# 12-_BLE_and_FLASH.net
KiCad netlist of a schematic drawn in Altium Designer
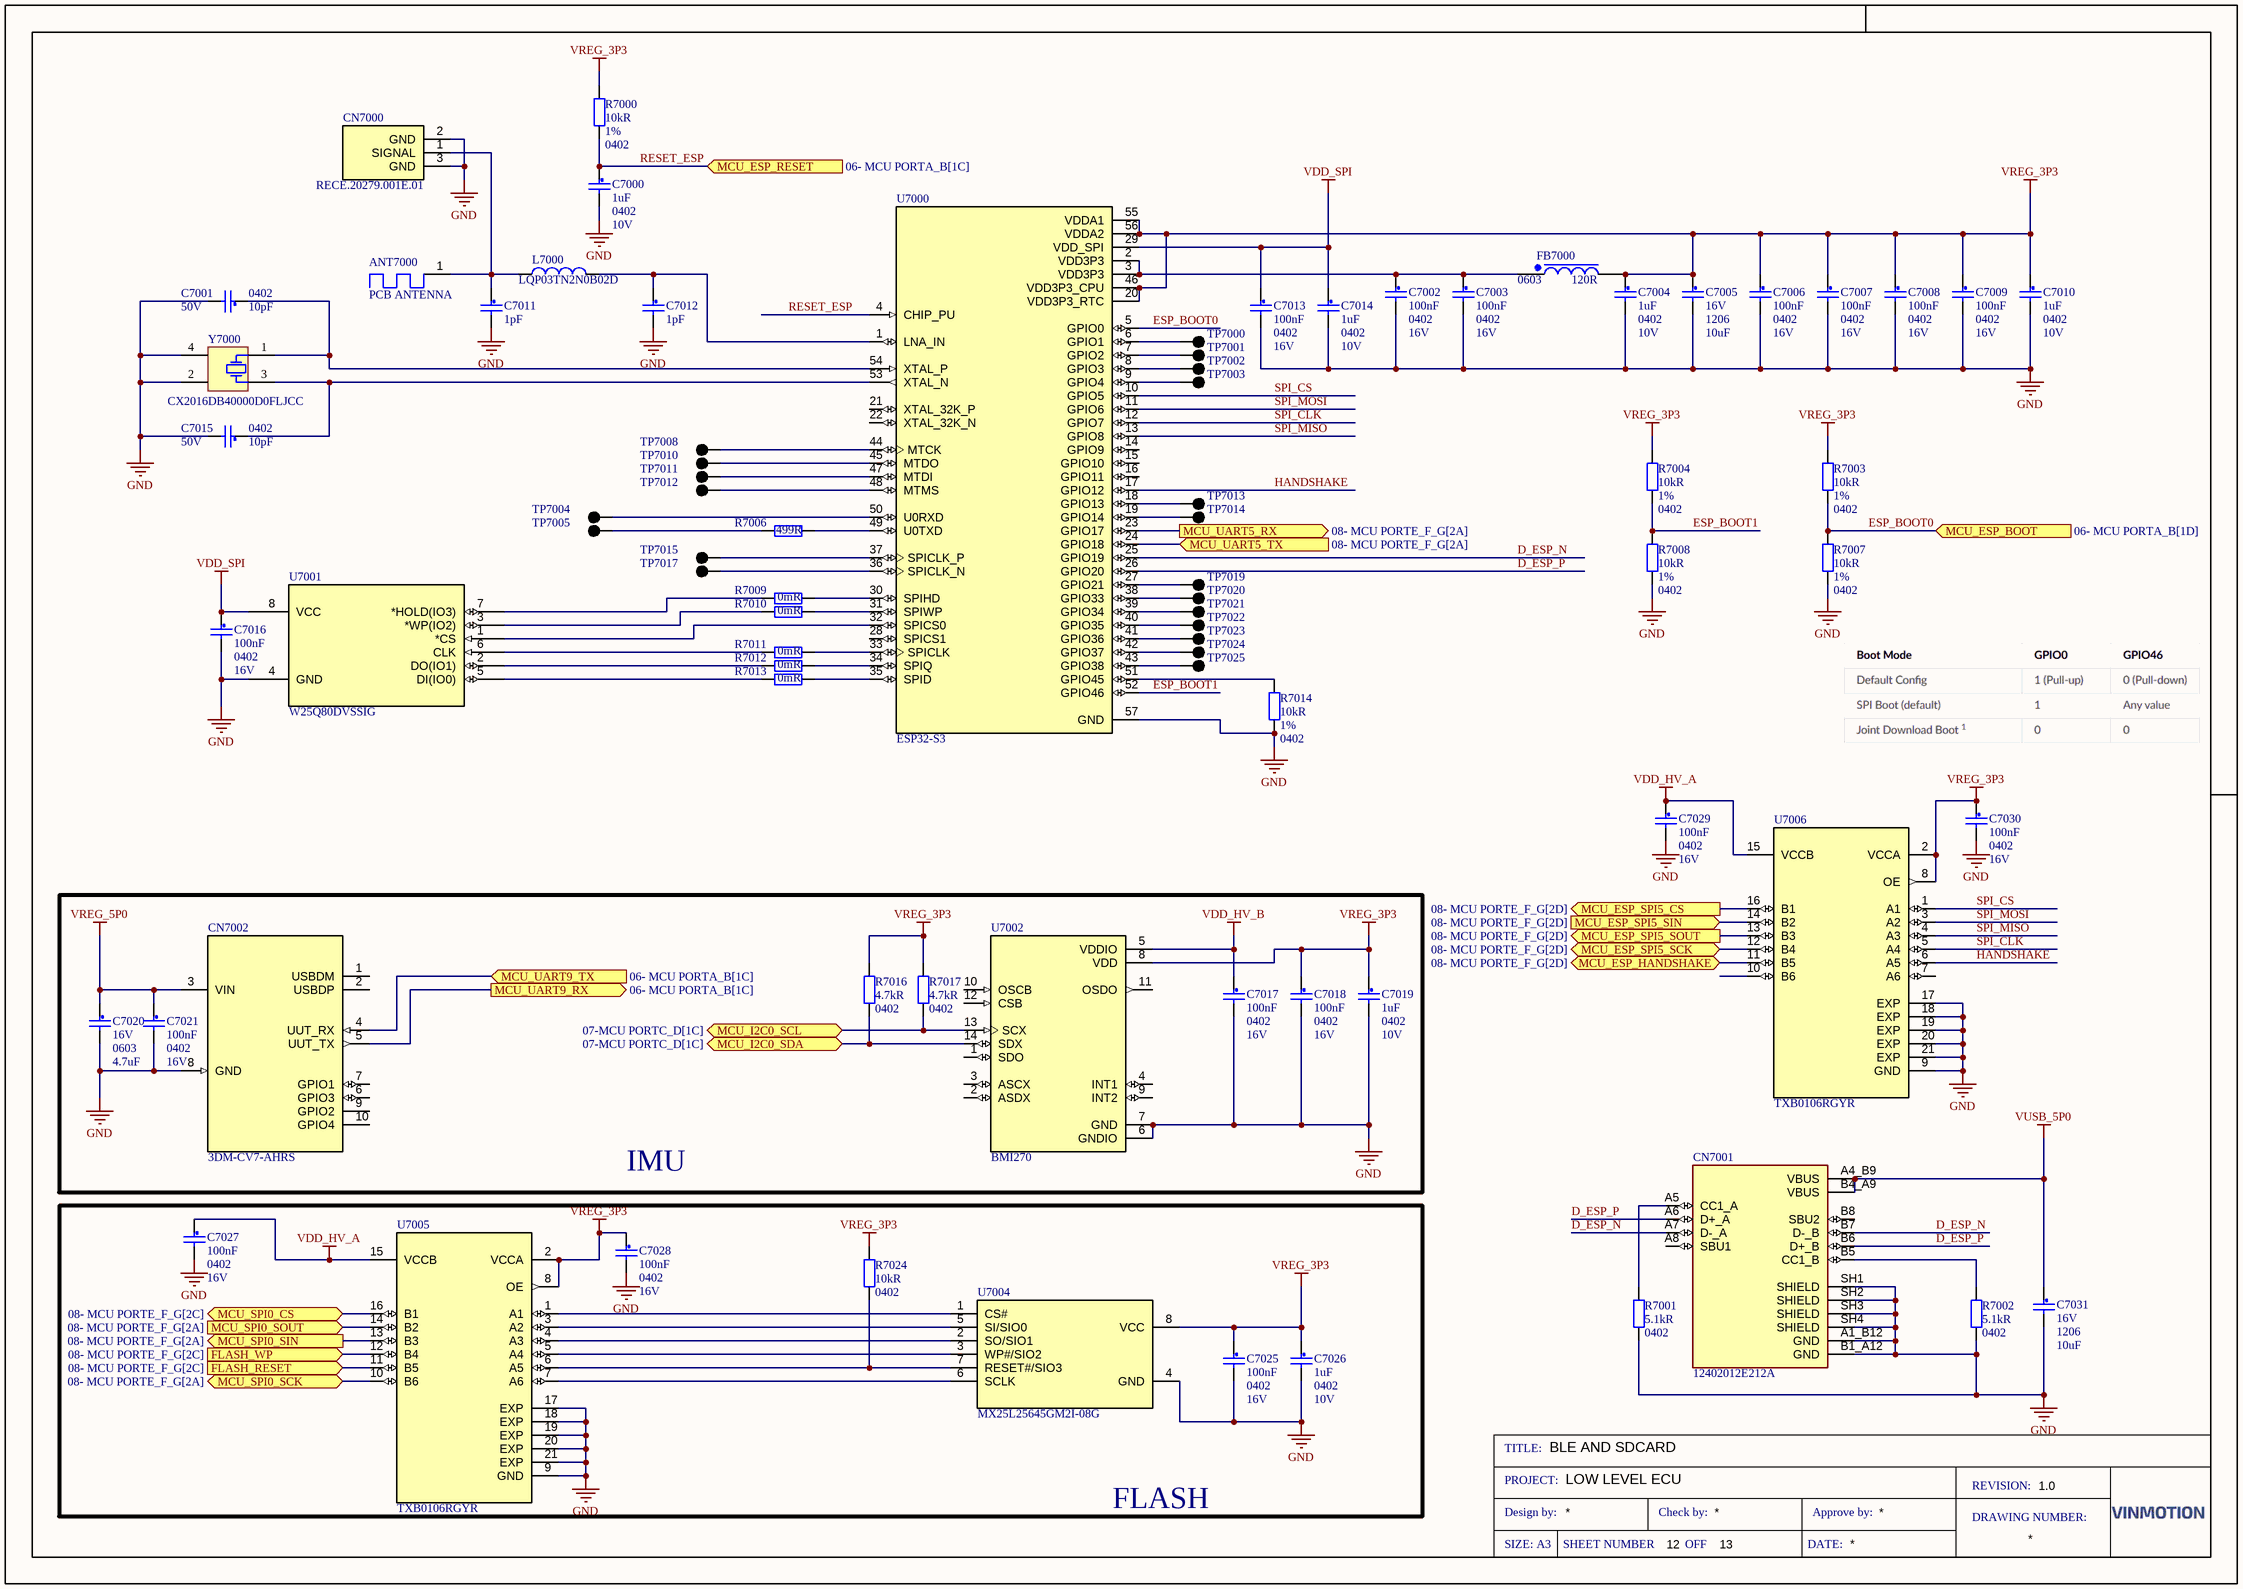
[diagram p0: 12- BLE and FLASH.SchDoc]

(export (version "E")
  (design (tool "Eeschema 10.0.6"))
  (components
    (comp (ref "ANT7000")
      (value "PCB ANTENNA")
      (footprint "ANTENNA 2.4G")
      (description "PCB ANTENNA 2.4G")
      (libsource (lib "VMO_Lib") (part "CMP-01139-1"))
    )
    (comp (ref "C7000")
      (value "1uF")
      (footprint "CAP0402")
      (description "CAP CER 1UF 10V X6S 0402")
      (fields
        (field (name "MANUFACTURER") "Samsung")
        (field (name "MANUFACTURER PART NUMBER") "CL05X105KP5NNNC")
        (field (name "CASE/PACKAGE") "0402")
        (field (name "RATED DC VOLTAGE (URDC)") "10V")
      )
      (libsource (lib "VMO_Lib") (part "CMP-01106-1"))
    )
    (comp (ref "C7001")
      (value "UMK105CG100DVHF")
      (footprint "CAP0402")
      (description "CAP CER 10pF 50V NP0 0402")
      (fields
        (field (name "VOLTAGE RATING") "50V")
        (field (name "CASE/PACKAGE") "0402")
        (field (name "CAPACITANCE") "10pF")
      )
      (libsource (lib "VMO_Lib") (part "CMP-00047-2"))
    )
    (comp (ref "C7002")
      (value "0402YC104KAT2A")
      (footprint "CAP0402")
      (description "CAP CER 0.1UF 16V X7R 0402")
      (fields
        (field (name "CAPACITANCE") "100nF")
        (field (name "CASE/PACKAGE") "0402")
        (field (name "VOLTAGE RATING (DC)") "16V")
      )
      (libsource (lib "VMO_Lib") (part "CMP-00988-1"))
    )
    (comp (ref "C7003")
      (value "0402YC104KAT2A")
      (footprint "CAP0402")
      (description "CAP CER 0.1UF 16V X7R 0402")
      (fields
        (field (name "CAPACITANCE") "100nF")
        (field (name "CASE/PACKAGE") "0402")
        (field (name "VOLTAGE RATING (DC)") "16V")
      )
      (libsource (lib "VMO_Lib") (part "CMP-00988-1"))
    )
    (comp (ref "C7004")
      (value "1uF")
      (footprint "CAP0402")
      (description "CAP CER 1UF 10V X6S 0402")
      (fields
        (field (name "MANUFACTURER") "Samsung")
        (field (name "MANUFACTURER PART NUMBER") "CL05X105KP5NNNC")
        (field (name "CASE/PACKAGE") "0402")
        (field (name "RATED DC VOLTAGE (URDC)") "10V")
      )
      (libsource (lib "VMO_Lib") (part "CMP-01106-1"))
    )
    (comp (ref "C7005")
      (value "CL31B106KOHVPNE")
      (footprint "CAP1206")
      (description "CAP CER 10uF 16V 10% X7R 1206 SMD")
      (fields
        (field (name "TOLERANCE") "10%")
        (field (name "VOLTAGE RATING") "16V")
        (field (name "CASE/PACKAGE") "1206")
        (field (name "CAPACITANCE") "10uF")
      )
      (libsource (lib "VMO_Lib") (part "CMP-00045-5"))
    )
    (comp (ref "C7006")
      (value "0402YC104KAT2A")
      (footprint "CAP0402")
      (description "CAP CER 0.1UF 16V X7R 0402")
      (fields
        (field (name "CAPACITANCE") "100nF")
        (field (name "CASE/PACKAGE") "0402")
        (field (name "VOLTAGE RATING (DC)") "16V")
      )
      (libsource (lib "VMO_Lib") (part "CMP-00988-1"))
    )
    (comp (ref "C7007")
      (value "0402YC104KAT2A")
      (footprint "CAP0402")
      (description "CAP CER 0.1UF 16V X7R 0402")
      (fields
        (field (name "CAPACITANCE") "100nF")
        (field (name "CASE/PACKAGE") "0402")
        (field (name "VOLTAGE RATING (DC)") "16V")
      )
      (libsource (lib "VMO_Lib") (part "CMP-00988-1"))
    )
    (comp (ref "C7008")
      (value "0402YC104KAT2A")
      (footprint "CAP0402")
      (description "CAP CER 0.1UF 16V X7R 0402")
      (fields
        (field (name "CAPACITANCE") "100nF")
        (field (name "CASE/PACKAGE") "0402")
        (field (name "VOLTAGE RATING (DC)") "16V")
      )
      (libsource (lib "VMO_Lib") (part "CMP-00988-1"))
    )
    (comp (ref "C7009")
      (value "0402YC104KAT2A")
      (footprint "CAP0402")
      (description "CAP CER 0.1UF 16V X7R 0402")
      (fields
        (field (name "CAPACITANCE") "100nF")
        (field (name "CASE/PACKAGE") "0402")
        (field (name "VOLTAGE RATING (DC)") "16V")
      )
      (libsource (lib "VMO_Lib") (part "CMP-00988-1"))
    )
    (comp (ref "C7010")
      (value "1uF")
      (footprint "CAP0402")
      (description "CAP CER 1UF 10V X6S 0402")
      (fields
        (field (name "MANUFACTURER") "Samsung")
        (field (name "MANUFACTURER PART NUMBER") "CL05X105KP5NNNC")
        (field (name "CASE/PACKAGE") "0402")
        (field (name "RATED DC VOLTAGE (URDC)") "10V")
      )
      (libsource (lib "VMO_Lib") (part "CMP-01106-1"))
    )
    (comp (ref "C7011")
      (value "1pF")
      (footprint "CAP0201")
      (description "CAP CER 1PF 50V C0G/NP0 0201")
      (fields
        (field (name "MANUFACTURER") "Murata")
        (field (name "MANUFACTURER PART NUMBER") "GRM0335C1H1R0BA01D")
      )
      (libsource (lib "VMO_Lib") (part "CMP-01137-1"))
    )
    (comp (ref "C7012")
      (value "1pF")
      (footprint "CAP0201")
      (description "CAP CER 1PF 50V C0G/NP0 0201")
      (fields
        (field (name "MANUFACTURER") "Murata")
        (field (name "MANUFACTURER PART NUMBER") "GRM0335C1H1R0BA01D")
      )
      (libsource (lib "VMO_Lib") (part "CMP-01137-1"))
    )
    (comp (ref "C7013")
      (value "0402YC104KAT2A")
      (footprint "CAP0402")
      (description "CAP CER 0.1UF 16V X7R 0402")
      (fields
        (field (name "CAPACITANCE") "100nF")
        (field (name "CASE/PACKAGE") "0402")
        (field (name "VOLTAGE RATING (DC)") "16V")
      )
      (libsource (lib "VMO_Lib") (part "CMP-00988-1"))
    )
    (comp (ref "C7014")
      (value "1uF")
      (footprint "CAP0402")
      (description "CAP CER 1UF 10V X6S 0402")
      (fields
        (field (name "MANUFACTURER") "Samsung")
        (field (name "MANUFACTURER PART NUMBER") "CL05X105KP5NNNC")
        (field (name "CASE/PACKAGE") "0402")
        (field (name "RATED DC VOLTAGE (URDC)") "10V")
      )
      (libsource (lib "VMO_Lib") (part "CMP-01106-1"))
    )
    (comp (ref "C7015")
      (value "UMK105CG100DVHF")
      (footprint "CAP0402")
      (description "CAP CER 10pF 50V NP0 0402")
      (fields
        (field (name "VOLTAGE RATING") "50V")
        (field (name "CASE/PACKAGE") "0402")
        (field (name "CAPACITANCE") "10pF")
      )
      (libsource (lib "VMO_Lib") (part "CMP-00047-2"))
    )
    (comp (ref "C7016")
      (value "0402YC104KAT2A")
      (footprint "CAP0402")
      (description "CAP CER 0.1UF 16V X7R 0402")
      (fields
        (field (name "CAPACITANCE") "100nF")
        (field (name "CASE/PACKAGE") "0402")
        (field (name "VOLTAGE RATING (DC)") "16V")
      )
      (libsource (lib "VMO_Lib") (part "CMP-00988-1"))
    )
    (comp (ref "C7017")
      (value "0402YC104KAT2A")
      (footprint "CAP0402")
      (description "CAP CER 0.1UF 16V X7R 0402")
      (fields
        (field (name "CAPACITANCE") "100nF")
        (field (name "CASE/PACKAGE") "0402")
        (field (name "VOLTAGE RATING (DC)") "16V")
      )
      (libsource (lib "VMO_Lib") (part "CMP-00988-1"))
    )
    (comp (ref "C7018")
      (value "0402YC104KAT2A")
      (footprint "CAP0402")
      (description "CAP CER 0.1UF 16V X7R 0402")
      (fields
        (field (name "CAPACITANCE") "100nF")
        (field (name "CASE/PACKAGE") "0402")
        (field (name "VOLTAGE RATING (DC)") "16V")
      )
      (libsource (lib "VMO_Lib") (part "CMP-00988-1"))
    )
    (comp (ref "C7019")
      (value "1uF")
      (footprint "CAP0402")
      (description "CAP CER 1UF 10V X6S 0402")
      (fields
        (field (name "MANUFACTURER") "Samsung")
        (field (name "MANUFACTURER PART NUMBER") "CL05X105KP5NNNC")
        (field (name "CASE/PACKAGE") "0402")
        (field (name "RATED DC VOLTAGE (URDC)") "10V")
      )
      (libsource (lib "VMO_Lib") (part "CMP-01106-1"))
    )
    (comp (ref "C7020")
      (value "GRT188C81C475KE13D")
      (footprint "CAP0603")
      (description "CAP CER 4.7uF 16V 10% X6S 0603 SMD")
      (fields
        (field (name "TOLERANCE") "10%")
        (field (name "VOLTAGE RATING") "16V")
        (field (name "CASE/PACKAGE") "0603")
        (field (name "CAPACITANCE") "4.7uF")
      )
      (libsource (lib "VMO_Lib") (part "CMP-00351-2"))
    )
    (comp (ref "C7021")
      (value "0402YC104KAT2A")
      (footprint "CAP0402")
      (description "CAP CER 0.1UF 16V X7R 0402")
      (fields
        (field (name "CAPACITANCE") "100nF")
        (field (name "CASE/PACKAGE") "0402")
        (field (name "VOLTAGE RATING (DC)") "16V")
      )
      (libsource (lib "VMO_Lib") (part "CMP-00988-1"))
    )
    (comp (ref "C7025")
      (value "0402YC104KAT2A")
      (footprint "CAP0402")
      (description "CAP CER 0.1UF 16V X7R 0402")
      (fields
        (field (name "CAPACITANCE") "100nF")
        (field (name "CASE/PACKAGE") "0402")
        (field (name "VOLTAGE RATING (DC)") "16V")
      )
      (libsource (lib "VMO_Lib") (part "CMP-00988-1"))
    )
    (comp (ref "C7026")
      (value "1uF")
      (footprint "CAP0402")
      (description "CAP CER 1UF 10V X6S 0402")
      (fields
        (field (name "MANUFACTURER") "Samsung")
        (field (name "MANUFACTURER PART NUMBER") "CL05X105KP5NNNC")
        (field (name "CASE/PACKAGE") "0402")
        (field (name "RATED DC VOLTAGE (URDC)") "10V")
      )
      (libsource (lib "VMO_Lib") (part "CMP-01106-1"))
    )
    (comp (ref "C7027")
      (value "0402YC104KAT2A")
      (footprint "CAP0402")
      (description "CAP CER 0.1UF 16V X7R 0402")
      (fields
        (field (name "CAPACITANCE") "100nF")
        (field (name "CASE/PACKAGE") "0402")
        (field (name "VOLTAGE RATING (DC)") "16V")
      )
      (libsource (lib "VMO_Lib") (part "CMP-00988-1"))
    )
    (comp (ref "C7028")
      (value "0402YC104KAT2A")
      (footprint "CAP0402")
      (description "CAP CER 0.1UF 16V X7R 0402")
      (fields
        (field (name "CAPACITANCE") "100nF")
        (field (name "CASE/PACKAGE") "0402")
        (field (name "VOLTAGE RATING (DC)") "16V")
      )
      (libsource (lib "VMO_Lib") (part "CMP-00988-1"))
    )
    (comp (ref "C7029")
      (value "0402YC104KAT2A")
      (footprint "CAP0402")
      (description "CAP CER 0.1UF 16V X7R 0402")
      (fields
        (field (name "CAPACITANCE") "100nF")
        (field (name "CASE/PACKAGE") "0402")
        (field (name "VOLTAGE RATING (DC)") "16V")
      )
      (libsource (lib "VMO_Lib") (part "CMP-00988-1"))
    )
    (comp (ref "C7030")
      (value "0402YC104KAT2A")
      (footprint "CAP0402")
      (description "CAP CER 0.1UF 16V X7R 0402")
      (fields
        (field (name "CAPACITANCE") "100nF")
        (field (name "CASE/PACKAGE") "0402")
        (field (name "VOLTAGE RATING (DC)") "16V")
      )
      (libsource (lib "VMO_Lib") (part "CMP-00988-1"))
    )
    (comp (ref "C7031")
      (value "CL31B106KOHVPNE")
      (footprint "CAP0603")
      (description "CAP CER 10uF 16V 10% X7R 1206 SMD")
      (fields
        (field (name "TOLERANCE") "10%")
        (field (name "VOLTAGE RATING") "16V")
        (field (name "CASE/PACKAGE") "1206")
        (field (name "CAPACITANCE") "10uF")
      )
      (libsource (lib "VMO_Lib") (part "CMP-00045-5"))
    )
    (comp (ref "CN7000")
      (value "RECE.20279.001E.01")
      (footprint "IPEX CONNECTOR")
      (description "CONN UMC RCPT STR 50 OHM SMD")
      (fields (field (name "MANUFACTURER") "Taoglas"))
      (libsource (lib "VMO_Lib") (part "CMP-01147-1"))
    )
    (comp (ref "CN7001")
      (value "12402012E212A")
      (footprint "USB_TYPE_C")
      (description "CONN RCP USB2.0 TYP C 24P SMD RA")
      (fields (field (name "MANUFACTURER") "Amphenol"))
      (libsource (lib "VMO_Lib") (part "CMP-01116-1"))
    )
    (comp (ref "CN7002")
      (value "3DM-CV7-AHRS")
      (footprint "3DM-CV7-AHRS")
      (description "IMUs - Inertial Measurement Units High Performance OEM IMU/AHRS")
      (fields (field (name "MANUFACTURER") "LORD"))
      (libsource (lib "VMO_Lib") (part "CMP-01131-1"))
    )
    (comp (ref "FB7000")
      (value "BLM18KG121TH1D")
      (footprint "FB0603")
      (description "FERRITE BEAD 120 OHM 0603 1LN")
      (fields (field (name "CASE/PACKAGE") "0603") (field (name "IMPEDANCE") "120R"))
      (libsource (lib "VMO_Lib") (part "CMP-ROOT-0013-6"))
    )
    (comp (ref "L7000")
      (value "LQP03TN2N0B02D")
      (footprint "IND0201")
      (description "FIXED IND 2NH 600MA 150 MOHM SMD")
      (fields (field (name "MANUFACTURER") "Murata") (field (name "TOLERANCE") "5%"))
      (libsource (lib "VMO_Lib") (part "CMP-01138-1"))
    )
    (comp (ref "R7000")
      (value "10kR")
      (footprint "RES0402")
      (description "RES 10K OHM 1% 1/16W 0402")
      (fields
        (field (name "MANUFACTURER") "Stackpole Electronics")
        (field (name "MANUFACTURER PART NUMBER") "RMCF0402FT10K0")
        (field (name "TOLERANCE") "1%")
        (field (name "CASE/PACKAGE") "0402")
      )
      (libsource (lib "VMO_Lib") (part "CMP-01105-1"))
    )
    (comp (ref "R7001")
      (value "MCR01MZPF5101")
      (footprint "RES0402")
      (description "RES SMD 5.1K OHM 1% 1/16W 0402")
      (fields
        (field (name "TOLERANCE") "1%")
        (field (name "RESISTANCE") "5.1kR")
        (field (name "CASE/PACKAGE") "0402")
      )
      (libsource (lib "VMO_Lib") (part "CMP-00289-1"))
    )
    (comp (ref "R7002")
      (value "MCR01MZPF5101")
      (footprint "RES0402")
      (description "RES SMD 5.1K OHM 1% 1/16W 0402")
      (fields
        (field (name "TOLERANCE") "1%")
        (field (name "RESISTANCE") "5.1kR")
        (field (name "CASE/PACKAGE") "0402")
      )
      (libsource (lib "VMO_Lib") (part "CMP-00289-1"))
    )
    (comp (ref "R7003")
      (value "10kR")
      (footprint "RES0402")
      (description "RES 10K OHM 1% 1/16W 0402")
      (fields
        (field (name "MANUFACTURER") "Stackpole Electronics")
        (field (name "MANUFACTURER PART NUMBER") "RMCF0402FT10K0")
        (field (name "TOLERANCE") "1%")
        (field (name "CASE/PACKAGE") "0402")
      )
      (libsource (lib "VMO_Lib") (part "CMP-01105-1"))
    )
    (comp (ref "R7004")
      (value "10kR")
      (footprint "RES0402")
      (description "RES 10K OHM 1% 1/16W 0402")
      (fields
        (field (name "MANUFACTURER") "Stackpole Electronics")
        (field (name "MANUFACTURER PART NUMBER") "RMCF0402FT10K0")
        (field (name "TOLERANCE") "1%")
        (field (name "CASE/PACKAGE") "0402")
      )
      (libsource (lib "VMO_Lib") (part "CMP-01105-1"))
    )
    (comp (ref "R7006")
      (value "499R")
      (footprint "RES0402")
      (description "RES SMD 499 OHM 1% 1/16W 0402")
      (fields
        (field (name "MANUFACTURER") "Vishay")
        (field (name "MANUFACTURER PART NUMBER") "CRCW0402499RFKED")
      )
      (libsource (lib "VMO_Lib") (part "CMP-01135-1"))
    )
    (comp (ref "R7007")
      (value "10kR")
      (footprint "RES0402")
      (description "RES 10K OHM 1% 1/16W 0402")
      (fields
        (field (name "MANUFACTURER") "Stackpole Electronics")
        (field (name "MANUFACTURER PART NUMBER") "RMCF0402FT10K0")
        (field (name "TOLERANCE") "1%")
        (field (name "CASE/PACKAGE") "0402")
      )
      (libsource (lib "VMO_Lib") (part "CMP-01105-1"))
    )
    (comp (ref "R7008")
      (value "10kR")
      (footprint "RES0402")
      (description "RES 10K OHM 1% 1/16W 0402")
      (fields
        (field (name "MANUFACTURER") "Stackpole Electronics")
        (field (name "MANUFACTURER PART NUMBER") "RMCF0402FT10K0")
        (field (name "TOLERANCE") "1%")
        (field (name "CASE/PACKAGE") "0402")
      )
      (libsource (lib "VMO_Lib") (part "CMP-01105-1"))
    )
    (comp (ref "R7009")
      (value "RMCF0402ZT0R00")
      (footprint "RES0402")
      (description "RES 0R 1/16W 1% 0402 SMD")
      (fields (field (name "RESISTANCE") "0mR"))
      (libsource (lib "VMO_Lib") (part "CMP-ROOT-0037-10"))
    )
    (comp (ref "R7010")
      (value "RMCF0402ZT0R00")
      (footprint "RES0402")
      (description "RES 0R 1/16W 1% 0402 SMD")
      (fields (field (name "RESISTANCE") "0mR"))
      (libsource (lib "VMO_Lib") (part "CMP-ROOT-0037-10"))
    )
    (comp (ref "R7011")
      (value "RMCF0402ZT0R00")
      (footprint "RES0402")
      (description "RES 0R 1/16W 1% 0402 SMD")
      (fields (field (name "RESISTANCE") "0mR"))
      (libsource (lib "VMO_Lib") (part "CMP-ROOT-0037-10"))
    )
    (comp (ref "R7012")
      (value "RMCF0402ZT0R00")
      (footprint "RES0402")
      (description "RES 0R 1/16W 1% 0402 SMD")
      (fields (field (name "RESISTANCE") "0mR"))
      (libsource (lib "VMO_Lib") (part "CMP-ROOT-0037-10"))
    )
    (comp (ref "R7013")
      (value "RMCF0402ZT0R00")
      (footprint "RES0402")
      (description "RES 0R 1/16W 1% 0402 SMD")
      (fields (field (name "RESISTANCE") "0mR"))
      (libsource (lib "VMO_Lib") (part "CMP-ROOT-0037-10"))
    )
    (comp (ref "R7014")
      (value "10kR")
      (footprint "RES0402")
      (description "RES 10K OHM 1% 1/16W 0402")
      (fields
        (field (name "MANUFACTURER") "Stackpole Electronics")
        (field (name "MANUFACTURER PART NUMBER") "RMCF0402FT10K0")
        (field (name "TOLERANCE") "1%")
        (field (name "CASE/PACKAGE") "0402")
      )
      (libsource (lib "VMO_Lib") (part "CMP-01105-1"))
    )
    (comp (ref "R7016")
      (value "RMCF0402FT4K70")
      (footprint "RES0402")
      (description "RES 4.7kR 1/16W 1% 0402 SMD")
      (fields
        (field (name "TOLERANCE") "1%")
        (field (name "RESISTANCE") "4.7kR")
        (field (name "CASE/PACKAGE") "0402")
      )
      (libsource (lib "VMO_Lib") (part "CMP-00354-2"))
    )
    (comp (ref "R7017")
      (value "RMCF0402FT4K70")
      (footprint "RES0402")
      (description "RES 4.7kR 1/16W 1% 0402 SMD")
      (fields
        (field (name "TOLERANCE") "1%")
        (field (name "RESISTANCE") "4.7kR")
        (field (name "CASE/PACKAGE") "0402")
      )
      (libsource (lib "VMO_Lib") (part "CMP-00354-2"))
    )
    (comp (ref "R7024")
      (value "ERJ2GEJ103X")
      (footprint "RES0402")
      (description "RES SMD 10K OHM 5% 1/10W 0402")
      (fields
        (field (name "TOLERANCE") "5%")
        (field (name "RESISTANCE") "10kR")
        (field (name "CASE/PACKAGE") "0402")
      )
      (libsource (lib "VMO_Lib") (part "CMP-00039-6"))
    )
    (comp (ref "TP7000")
      (value "TP")
      (footprint "TP-SMD-R1")
      (description "Test Point 1x1mm")
      (libsource (lib "VMO_Lib") (part "CMP-ROOT-0080-12"))
    )
    (comp (ref "TP7001")
      (value "TP")
      (footprint "TP-SMD-R1")
      (description "Test Point 1x1mm")
      (libsource (lib "VMO_Lib") (part "CMP-ROOT-0080-12"))
    )
    (comp (ref "TP7002")
      (value "TP")
      (footprint "TP-SMD-R1")
      (description "Test Point 1x1mm")
      (libsource (lib "VMO_Lib") (part "CMP-ROOT-0080-12"))
    )
    (comp (ref "TP7003")
      (value "TP")
      (footprint "TP-SMD-R1")
      (description "Test Point 1x1mm")
      (libsource (lib "VMO_Lib") (part "CMP-ROOT-0080-12"))
    )
    (comp (ref "TP7004")
      (value "TP")
      (footprint "TP-SMD-R1")
      (description "Test Point 1x1mm")
      (libsource (lib "VMO_Lib") (part "CMP-ROOT-0080-12"))
    )
    (comp (ref "TP7005")
      (value "TP")
      (footprint "TP-SMD-R1")
      (description "Test Point 1x1mm")
      (libsource (lib "VMO_Lib") (part "CMP-ROOT-0080-12"))
    )
    (comp (ref "TP7008")
      (value "TP")
      (footprint "TP-SMD-R1")
      (description "Test Point 1x1mm")
      (libsource (lib "VMO_Lib") (part "CMP-ROOT-0080-12"))
    )
    (comp (ref "TP7010")
      (value "TP")
      (footprint "TP-SMD-R1")
      (description "Test Point 1x1mm")
      (libsource (lib "VMO_Lib") (part "CMP-ROOT-0080-12"))
    )
    (comp (ref "TP7011")
      (value "TP")
      (footprint "TP-SMD-R1")
      (description "Test Point 1x1mm")
      (libsource (lib "VMO_Lib") (part "CMP-ROOT-0080-12"))
    )
    (comp (ref "TP7012")
      (value "TP")
      (footprint "TP-SMD-R1")
      (description "Test Point 1x1mm")
      (libsource (lib "VMO_Lib") (part "CMP-ROOT-0080-12"))
    )
    (comp (ref "TP7013")
      (value "TP")
      (footprint "TP-SMD-R1")
      (description "Test Point 1x1mm")
      (libsource (lib "VMO_Lib") (part "CMP-ROOT-0080-12"))
    )
    (comp (ref "TP7014")
      (value "TP")
      (footprint "TP-SMD-R1")
      (description "Test Point 1x1mm")
      (libsource (lib "VMO_Lib") (part "CMP-ROOT-0080-12"))
    )
    (comp (ref "TP7015")
      (value "TP")
      (footprint "TP-SMD-R1")
      (description "Test Point 1x1mm")
      (libsource (lib "VMO_Lib") (part "CMP-ROOT-0080-12"))
    )
    (comp (ref "TP7017")
      (value "TP")
      (footprint "TP-SMD-R1")
      (description "Test Point 1x1mm")
      (libsource (lib "VMO_Lib") (part "CMP-ROOT-0080-12"))
    )
    (comp (ref "TP7019")
      (value "TP")
      (footprint "TP-SMD-R1")
      (description "Test Point 1x1mm")
      (libsource (lib "VMO_Lib") (part "CMP-ROOT-0080-12"))
    )
    (comp (ref "TP7020")
      (value "TP")
      (footprint "TP-SMD-R1")
      (description "Test Point 1x1mm")
      (libsource (lib "VMO_Lib") (part "CMP-ROOT-0080-12"))
    )
    (comp (ref "TP7021")
      (value "TP")
      (footprint "TP-SMD-R1")
      (description "Test Point 1x1mm")
      (libsource (lib "VMO_Lib") (part "CMP-ROOT-0080-12"))
    )
    (comp (ref "TP7022")
      (value "TP")
      (footprint "TP-SMD-R1")
      (description "Test Point 1x1mm")
      (libsource (lib "VMO_Lib") (part "CMP-ROOT-0080-12"))
    )
    (comp (ref "TP7023")
      (value "TP")
      (footprint "TP-SMD-R1")
      (description "Test Point 1x1mm")
      (libsource (lib "VMO_Lib") (part "CMP-ROOT-0080-12"))
    )
    (comp (ref "TP7024")
      (value "TP")
      (footprint "TP-SMD-R1")
      (description "Test Point 1x1mm")
      (libsource (lib "VMO_Lib") (part "CMP-ROOT-0080-12"))
    )
    (comp (ref "TP7025")
      (value "TP")
      (footprint "TP-SMD-R1")
      (description "Test Point 1x1mm")
      (libsource (lib "VMO_Lib") (part "CMP-ROOT-0080-12"))
    )
    (comp (ref "U7000")
      (value "ESP32-S3")
      (footprint "56-VFQFN Exposed Pad")
      (description "IC RF TXRX+MCU BLE 56QFN")
      (fields
        (field (name "MANUFACTURER") "Espressif Systems")
        (field (name "MANUFACTURER PART NUMBER") "ESP32-S3R8")
      )
      (libsource (lib "VMO_Lib") (part "CMP-01132-1"))
    )
    (comp (ref "U7001")
      (value "W25Q80DVSSIG")
      (footprint "SOIC127P800X216-8N")
      (description "IC FLASH 8MBIT SPI/QUAD 8SOIC")
      (fields (field (name "MANUFACTURER") "Winbond"))
      (libsource (lib "VMO_Lib") (part "CMP-01134-1"))
    )
    (comp (ref "U7002")
      (value "BMI270")
      (footprint "BIN270")
      (description "IMU ACCEL/GYRO I2C/SPI 14LGA")
      (fields (field (name "MANUFACTURER") "Bosch Sensortec"))
      (libsource (lib "VMO_Lib") (part "CMP-01130-1"))
    )
    (comp (ref "U7004")
      (value "MX25L25645GM2I-08G")
      (footprint "SOIC127P800X175-8N")
      (description "IC FLASH 256MBIT SPI 120MHZ 8SOP")
      (fields (field (name "MANUFACTURER") "Macronix"))
      (libsource (lib "VMO_Lib") (part "CMP-01188-1"))
    )
    (comp (ref "U7005")
      (value "TXB0106RGYR")
      (footprint "16-VFQFN Exposed Pad")
      (description "IC VOLTAGE LEVEL BIDIR 16-VQFN")
      (fields (field (name "MANUFACTURER") "Texas Instruments"))
      (libsource (lib "VMO_Lib") (part "CMP-01197-1"))
    )
    (comp (ref "U7006")
      (value "TXB0106RGYR")
      (footprint "16-VFQFN Exposed Pad")
      (description "IC VOLTAGE LEVEL BIDIR 16-VQFN")
      (fields (field (name "MANUFACTURER") "Texas Instruments"))
      (libsource (lib "VMO_Lib") (part "CMP-01197-1"))
    )
    (comp (ref "Y7000")
      (value "CX2016DB40000D0FLJCC")
      (footprint "CRYSTAL2016")
      (description "CRYSTAL 40.0000MHZ 8PF SMD")
      (fields (field (name "MANUFACTURER") "Kyocera AVX"))
      (libsource (lib "VMO_Lib") (part "CMP-01136-1"))
    )
  )
  (nets
    (net (code "1") (name "/D_ESP_N") (class "Default")
      (node (ref "CN7001") (pin "A7") (pinfunction "D-_A_A7") (pintype "bidirectional"))
      (node (ref "CN7001") (pin "B7") (pinfunction "D-_B_B7") (pintype "bidirectional"))
      (node (ref "U7000") (pin "25") (pinfunction "GPIO19_25") (pintype "bidirectional"))
    )
    (net (code "2") (name "/D_ESP_P") (class "Default")
      (node (ref "CN7001") (pin "A6") (pinfunction "D+_A_A6") (pintype "bidirectional"))
      (node (ref "CN7001") (pin "B6") (pinfunction "D+_B_B6") (pintype "bidirectional"))
      (node (ref "U7000") (pin "26") (pinfunction "GPIO20_26") (pintype "bidirectional"))
    )
    (net (code "3") (name "/ESP_BOOT0") (class "Default")
      (node (ref "R7003") (pin "1") (pinfunction "1_1") (pintype "passive"))
      (node (ref "R7007") (pin "2") (pinfunction "2_2") (pintype "passive"))
      (node (ref "U7000") (pin "5") (pinfunction "GPIO0_5") (pintype "bidirectional"))
    )
    (net (code "4") (name "/ESP_BOOT1") (class "Default")
      (node (ref "R7004") (pin "1") (pinfunction "1_1") (pintype "passive"))
      (node (ref "R7008") (pin "2") (pinfunction "2_2") (pintype "passive"))
      (node (ref "U7000") (pin "52") (pinfunction "GPIO46_52") (pintype "bidirectional"))
    )
    (net (code "5") (name "/FLASH_RESET") (class "Default")
      (node (ref "U7005") (pin "11") (pinfunction "B5_11") (pintype "bidirectional"))
    )
    (net (code "6") (name "/FLASH_WP") (class "Default")
      (node (ref "U7005") (pin "12") (pinfunction "B4_12") (pintype "bidirectional"))
    )
    (net (code "7") (name "/HANDSHAKE") (class "Default")
      (node (ref "U7000") (pin "17") (pinfunction "GPIO12_17") (pintype "bidirectional"))
      (node (ref "U7006") (pin "6") (pinfunction "A5_6") (pintype "bidirectional"))
    )
    (net (code "8") (name "/MCU_ESP_HANDSHAKE") (class "Default")
      (node (ref "U7006") (pin "11") (pinfunction "B5_11") (pintype "bidirectional"))
    )
    (net (code "9") (name "/MCU_ESP_SPI5_CS") (class "Default")
      (node (ref "U7006") (pin "16") (pinfunction "B1_16") (pintype "bidirectional"))
    )
    (net (code "10") (name "/MCU_ESP_SPI5_SCK") (class "Default")
      (node (ref "U7006") (pin "12") (pinfunction "B4_12") (pintype "bidirectional"))
    )
    (net (code "11") (name "/MCU_ESP_SPI5_SIN") (class "Default")
      (node (ref "U7006") (pin "14") (pinfunction "B2_14") (pintype "bidirectional"))
    )
    (net (code "12") (name "/MCU_ESP_SPI5_SOUT") (class "Default")
      (node (ref "U7006") (pin "13") (pinfunction "B3_13") (pintype "bidirectional"))
    )
    (net (code "13") (name "/MCU_I2C0_SCL") (class "Default")
      (node (ref "R7017") (pin "1") (pinfunction "1_1") (pintype "passive"))
      (node (ref "U7002") (pin "13") (pinfunction "SCX_13") (pintype "input"))
    )
    (net (code "14") (name "/MCU_I2C0_SDA") (class "Default")
      (node (ref "R7016") (pin "1") (pinfunction "1_1") (pintype "passive"))
      (node (ref "U7002") (pin "14") (pinfunction "SDX_14") (pintype "bidirectional"))
    )
    (net (code "15") (name "/MCU_SPI0_CS") (class "Default")
      (node (ref "U7005") (pin "16") (pinfunction "B1_16") (pintype "bidirectional"))
    )
    (net (code "16") (name "/MCU_SPI0_SCK") (class "Default")
      (node (ref "U7005") (pin "10") (pinfunction "B6_10") (pintype "bidirectional"))
    )
    (net (code "17") (name "/MCU_SPI0_SIN") (class "Default")
      (node (ref "U7005") (pin "13") (pinfunction "B3_13") (pintype "bidirectional"))
    )
    (net (code "18") (name "/MCU_SPI0_SOUT") (class "Default")
      (node (ref "U7005") (pin "14") (pinfunction "B2_14") (pintype "bidirectional"))
    )
    (net (code "19") (name "/MCU_UART5_RX") (class "Default")
      (node (ref "U7000") (pin "23") (pinfunction "GPIO17_23") (pintype "bidirectional"))
    )
    (net (code "20") (name "/MCU_UART5_TX") (class "Default")
      (node (ref "U7000") (pin "24") (pinfunction "GPIO18_24") (pintype "bidirectional"))
    )
    (net (code "21") (name "/MCU_UART9_RX") (class "Default")
      (node (ref "CN7002") (pin "5") (pinfunction "UUT_TX_5") (pintype "output"))
    )
    (net (code "22") (name "/MCU_UART9_TX") (class "Default")
      (node (ref "CN7002") (pin "4") (pinfunction "UUT_RX_4") (pintype "input"))
    )
    (net (code "23") (name "/RESET_ESP") (class "Default")
      (node (ref "C7000") (pin "1") (pinfunction "1_1") (pintype "passive"))
      (node (ref "R7000") (pin "1") (pinfunction "1_1") (pintype "passive"))
      (node (ref "U7000") (pin "4") (pinfunction "CHIP_PU_4") (pintype "input"))
    )
    (net (code "24") (name "/SPI_CLK") (class "Default")
      (node (ref "U7000") (pin "12") (pinfunction "GPIO7_12") (pintype "bidirectional"))
      (node (ref "U7006") (pin "5") (pinfunction "A4_5") (pintype "bidirectional"))
    )
    (net (code "25") (name "/SPI_CS") (class "Default")
      (node (ref "U7000") (pin "10") (pinfunction "GPIO5_10") (pintype "bidirectional"))
      (node (ref "U7006") (pin "1") (pinfunction "A1_1") (pintype "bidirectional"))
    )
    (net (code "26") (name "/SPI_MISO") (class "Default")
      (node (ref "U7000") (pin "13") (pinfunction "GPIO8_13") (pintype "bidirectional"))
      (node (ref "U7006") (pin "4") (pinfunction "A3_4") (pintype "bidirectional"))
    )
    (net (code "27") (name "/SPI_MOSI") (class "Default")
      (node (ref "U7000") (pin "11") (pinfunction "GPIO6_11") (pintype "bidirectional"))
      (node (ref "U7006") (pin "3") (pinfunction "A2_3") (pintype "bidirectional"))
    )
    (net (code "28") (name "GND") (class "Default")
      (node (ref "C7000") (pin "2") (pinfunction "2_2") (pintype "passive"))
      (node (ref "C7001") (pin "2") (pinfunction "2_2") (pintype "passive"))
      (node (ref "C7002") (pin "2") (pinfunction "2_2") (pintype "passive"))
      (node (ref "C7003") (pin "2") (pinfunction "2_2") (pintype "passive"))
      (node (ref "C7004") (pin "2") (pinfunction "2_2") (pintype "passive"))
      (node (ref "C7005") (pin "2") (pinfunction "2_2") (pintype "passive"))
      (node (ref "C7006") (pin "2") (pinfunction "2_2") (pintype "passive"))
      (node (ref "C7007") (pin "2") (pinfunction "2_2") (pintype "passive"))
      (node (ref "C7008") (pin "2") (pinfunction "2_2") (pintype "passive"))
      (node (ref "C7009") (pin "2") (pinfunction "2_2") (pintype "passive"))
      (node (ref "C7010") (pin "2") (pinfunction "2_2") (pintype "passive"))
      (node (ref "C7011") (pin "2") (pinfunction "2_2") (pintype "passive"))
      (node (ref "C7012") (pin "2") (pinfunction "2_2") (pintype "passive"))
      (node (ref "C7013") (pin "2") (pinfunction "2_2") (pintype "passive"))
      (node (ref "C7014") (pin "2") (pinfunction "2_2") (pintype "passive"))
      (node (ref "C7015") (pin "2") (pinfunction "2_2") (pintype "passive"))
      (node (ref "C7016") (pin "2") (pinfunction "2_2") (pintype "passive"))
      (node (ref "C7017") (pin "2") (pinfunction "2_2") (pintype "passive"))
      (node (ref "C7018") (pin "2") (pinfunction "2_2") (pintype "passive"))
      (node (ref "C7019") (pin "2") (pinfunction "2_2") (pintype "passive"))
      (node (ref "C7020") (pin "2") (pinfunction "2_2") (pintype "passive"))
      (node (ref "C7021") (pin "2") (pinfunction "2_2") (pintype "passive"))
      (node (ref "C7025") (pin "2") (pinfunction "2_2") (pintype "passive"))
      (node (ref "C7026") (pin "2") (pinfunction "2_2") (pintype "passive"))
      (node (ref "C7027") (pin "2") (pinfunction "2_2") (pintype "passive"))
      (node (ref "C7028") (pin "2") (pinfunction "2_2") (pintype "passive"))
      (node (ref "C7029") (pin "2") (pinfunction "2_2") (pintype "passive"))
      (node (ref "C7030") (pin "2") (pinfunction "2_2") (pintype "passive"))
      (node (ref "C7031") (pin "2") (pinfunction "2_2") (pintype "passive"))
      (node (ref "CN7000") (pin "2") (pinfunction "GND_2") (pintype "passive"))
      (node (ref "CN7000") (pin "3") (pinfunction "GND_3") (pintype "passive"))
      (node (ref "CN7001") (pin "A1_B12") (pinfunction "GND_A1_B12") (pintype "power_in"))
      (node (ref "CN7001") (pin "B1_A12") (pinfunction "GND_B1_A12") (pintype "power_in"))
      (node (ref "CN7001") (pin "SH1") (pinfunction "SHIELD_SH1") (pintype "passive"))
      (node (ref "CN7001") (pin "SH2") (pinfunction "SHIELD_SH2") (pintype "passive"))
      (node (ref "CN7001") (pin "SH3") (pinfunction "SHIELD_SH3") (pintype "passive"))
      (node (ref "CN7001") (pin "SH4") (pinfunction "SHIELD_SH4") (pintype "passive"))
      (node (ref "CN7002") (pin "8") (pinfunction "GND_8") (pintype "input"))
      (node (ref "R7001") (pin "1") (pinfunction "1_1") (pintype "passive"))
      (node (ref "R7002") (pin "1") (pinfunction "1_1") (pintype "passive"))
      (node (ref "R7007") (pin "1") (pinfunction "1_1") (pintype "passive"))
      (node (ref "R7008") (pin "1") (pinfunction "1_1") (pintype "passive"))
      (node (ref "R7014") (pin "1") (pinfunction "1_1") (pintype "passive"))
      (node (ref "U7000") (pin "57") (pinfunction "GND_57") (pintype "power_in"))
      (node (ref "U7001") (pin "4") (pinfunction "GND_4") (pintype "power_in"))
      (node (ref "U7002") (pin "6") (pinfunction "GNDIO_6") (pintype "power_in"))
      (node (ref "U7002") (pin "7") (pinfunction "GND_7") (pintype "power_in"))
      (node (ref "U7004") (pin "4") (pinfunction "GND_4") (pintype "passive"))
      (node (ref "U7005") (pin "17") (pinfunction "EXP_17") (pintype "passive"))
      (node (ref "U7005") (pin "18") (pinfunction "EXP_18") (pintype "passive"))
      (node (ref "U7005") (pin "19") (pinfunction "EXP_19") (pintype "passive"))
      (node (ref "U7005") (pin "20") (pinfunction "EXP_20") (pintype "passive"))
      (node (ref "U7005") (pin "21") (pinfunction "EXP_21") (pintype "passive"))
      (node (ref "U7005") (pin "9") (pinfunction "GND_9") (pintype "power_in"))
      (node (ref "U7006") (pin "17") (pinfunction "EXP_17") (pintype "passive"))
      (node (ref "U7006") (pin "18") (pinfunction "EXP_18") (pintype "passive"))
      (node (ref "U7006") (pin "19") (pinfunction "EXP_19") (pintype "passive"))
      (node (ref "U7006") (pin "20") (pinfunction "EXP_20") (pintype "passive"))
      (node (ref "U7006") (pin "21") (pinfunction "EXP_21") (pintype "passive"))
      (node (ref "U7006") (pin "9") (pinfunction "GND_9") (pintype "power_in"))
      (node (ref "Y7000") (pin "2") (pinfunction "GND_2") (pintype "passive"))
      (node (ref "Y7000") (pin "4") (pinfunction "GND_4") (pintype "passive"))
    )
    (net (code "29") (name "Net-(ANT7000-ANT)") (class "Default")
      (node (ref "ANT7000") (pin "1") (pinfunction "ANT_1") (pintype "passive"))
      (node (ref "C7011") (pin "1") (pinfunction "1_1") (pintype "passive"))
      (node (ref "CN7000") (pin "1") (pinfunction "SIGNAL_1") (pintype "passive"))
      (node (ref "L7000") (pin "1") (pinfunction "1_1") (pintype "passive"))
    )
    (net (code "30") (name "Net-(C7002-Pad1)") (class "Default")
      (node (ref "C7002") (pin "1") (pinfunction "1_1") (pintype "passive"))
      (node (ref "C7003") (pin "1") (pinfunction "1_1") (pintype "passive"))
      (node (ref "FB7000") (pin "1") (pinfunction "1_1") (pintype "passive"))
      (node (ref "U7000") (pin "2") (pinfunction "VDD3P3_2") (pintype "power_in"))
      (node (ref "U7000") (pin "3") (pinfunction "VDD3P3_3") (pintype "power_in"))
    )
    (net (code "31") (name "Net-(CN7001-CC1_A)") (class "Default")
      (node (ref "CN7001") (pin "A5") (pinfunction "CC1_A_A5") (pintype "bidirectional"))
      (node (ref "R7001") (pin "2") (pinfunction "2_2") (pintype "passive"))
    )
    (net (code "32") (name "Net-(CN7001-CC1_B)") (class "Default")
      (node (ref "CN7001") (pin "B5") (pinfunction "CC1_B_B5") (pintype "bidirectional"))
      (node (ref "R7002") (pin "2") (pinfunction "2_2") (pintype "passive"))
    )
    (net (code "33") (name "Net-(R7006-Pad2)") (class "Default")
      (node (ref "R7006") (pin "2") (pinfunction "2_2") (pintype "passive"))
      (node (ref "TP7005") (pin "1") (pinfunction "1_1") (pintype "passive"))
    )
    (net (code "34") (name "Net-(U7000-GPIO1)") (class "Default")
      (node (ref "TP7000") (pin "1") (pinfunction "1_1") (pintype "passive"))
      (node (ref "U7000") (pin "6") (pinfunction "GPIO1_6") (pintype "bidirectional"))
    )
    (net (code "35") (name "Net-(U7000-GPIO2)") (class "Default")
      (node (ref "TP7001") (pin "1") (pinfunction "1_1") (pintype "passive"))
      (node (ref "U7000") (pin "7") (pinfunction "GPIO2_7") (pintype "bidirectional"))
    )
    (net (code "36") (name "Net-(U7000-GPIO3)") (class "Default")
      (node (ref "TP7002") (pin "1") (pinfunction "1_1") (pintype "passive"))
      (node (ref "U7000") (pin "8") (pinfunction "GPIO3_8") (pintype "bidirectional"))
    )
    (net (code "37") (name "Net-(U7000-GPIO4)") (class "Default")
      (node (ref "TP7003") (pin "1") (pinfunction "1_1") (pintype "passive"))
      (node (ref "U7000") (pin "9") (pinfunction "GPIO4_9") (pintype "bidirectional"))
    )
    (net (code "38") (name "Net-(U7000-GPIO13)") (class "Default")
      (node (ref "TP7013") (pin "1") (pinfunction "1_1") (pintype "passive"))
      (node (ref "U7000") (pin "18") (pinfunction "GPIO13_18") (pintype "bidirectional"))
    )
    (net (code "39") (name "Net-(U7000-GPIO14)") (class "Default")
      (node (ref "TP7014") (pin "1") (pinfunction "1_1") (pintype "passive"))
      (node (ref "U7000") (pin "19") (pinfunction "GPIO14_19") (pintype "bidirectional"))
    )
    (net (code "40") (name "Net-(U7000-GPIO21)") (class "Default")
      (node (ref "TP7019") (pin "1") (pinfunction "1_1") (pintype "passive"))
      (node (ref "U7000") (pin "27") (pinfunction "GPIO21_27") (pintype "bidirectional"))
    )
    (net (code "41") (name "Net-(U7000-GPIO33)") (class "Default")
      (node (ref "TP7020") (pin "1") (pinfunction "1_1") (pintype "passive"))
      (node (ref "U7000") (pin "38") (pinfunction "GPIO33_38") (pintype "bidirectional"))
    )
    (net (code "42") (name "Net-(U7000-GPIO34)") (class "Default")
      (node (ref "TP7021") (pin "1") (pinfunction "1_1") (pintype "passive"))
      (node (ref "U7000") (pin "39") (pinfunction "GPIO34_39") (pintype "bidirectional"))
    )
    (net (code "43") (name "Net-(U7000-GPIO35)") (class "Default")
      (node (ref "TP7022") (pin "1") (pinfunction "1_1") (pintype "passive"))
      (node (ref "U7000") (pin "40") (pinfunction "GPIO35_40") (pintype "bidirectional"))
    )
    (net (code "44") (name "Net-(U7000-GPIO36)") (class "Default")
      (node (ref "TP7023") (pin "1") (pinfunction "1_1") (pintype "passive"))
      (node (ref "U7000") (pin "41") (pinfunction "GPIO36_41") (pintype "bidirectional"))
    )
    (net (code "45") (name "Net-(U7000-GPIO37)") (class "Default")
      (node (ref "TP7024") (pin "1") (pinfunction "1_1") (pintype "passive"))
      (node (ref "U7000") (pin "42") (pinfunction "GPIO37_42") (pintype "bidirectional"))
    )
    (net (code "46") (name "Net-(U7000-GPIO38)") (class "Default")
      (node (ref "TP7025") (pin "1") (pinfunction "1_1") (pintype "passive"))
      (node (ref "U7000") (pin "43") (pinfunction "GPIO38_43") (pintype "bidirectional"))
    )
    (net (code "47") (name "Net-(U7000-GPIO45)") (class "Default")
      (node (ref "R7014") (pin "2") (pinfunction "2_2") (pintype "passive"))
      (node (ref "U7000") (pin "51") (pinfunction "GPIO45_51") (pintype "bidirectional"))
    )
    (net (code "48") (name "Net-(U7000-LNA_IN)") (class "Default")
      (node (ref "C7012") (pin "1") (pinfunction "1_1") (pintype "passive"))
      (node (ref "L7000") (pin "2") (pinfunction "2_2") (pintype "passive"))
      (node (ref "U7000") (pin "1") (pinfunction "LNA_IN_1") (pintype "bidirectional"))
    )
    (net (code "49") (name "Net-(U7000-MTCK)") (class "Default")
      (node (ref "TP7008") (pin "1") (pinfunction "1_1") (pintype "passive"))
      (node (ref "U7000") (pin "44") (pinfunction "MTCK_44") (pintype "bidirectional"))
    )
    (net (code "50") (name "Net-(U7000-MTDI)") (class "Default")
      (node (ref "TP7011") (pin "1") (pinfunction "1_1") (pintype "passive"))
      (node (ref "U7000") (pin "47") (pinfunction "MTDI_47") (pintype "bidirectional"))
    )
    (net (code "51") (name "Net-(U7000-MTDO)") (class "Default")
      (node (ref "TP7010") (pin "1") (pinfunction "1_1") (pintype "passive"))
      (node (ref "U7000") (pin "45") (pinfunction "MTDO_45") (pintype "bidirectional"))
    )
    (net (code "52") (name "Net-(U7000-MTMS)") (class "Default")
      (node (ref "TP7012") (pin "1") (pinfunction "1_1") (pintype "passive"))
      (node (ref "U7000") (pin "48") (pinfunction "MTMS_48") (pintype "bidirectional"))
    )
    (net (code "53") (name "Net-(U7000-SPICLK)") (class "Default")
      (node (ref "R7011") (pin "2") (pinfunction "2_2") (pintype "passive"))
      (node (ref "U7000") (pin "33") (pinfunction "SPICLK_33") (pintype "bidirectional"))
    )
    (net (code "54") (name "Net-(U7000-SPICLK_N)") (class "Default")
      (node (ref "TP7017") (pin "1") (pinfunction "1_1") (pintype "passive"))
      (node (ref "U7000") (pin "36") (pinfunction "SPICLK_N_36") (pintype "bidirectional"))
    )
    (net (code "55") (name "Net-(U7000-SPICLK_P)") (class "Default")
      (node (ref "TP7015") (pin "1") (pinfunction "1_1") (pintype "passive"))
      (node (ref "U7000") (pin "37") (pinfunction "SPICLK_P_37") (pintype "bidirectional"))
    )
    (net (code "56") (name "Net-(U7000-SPICS0)") (class "Default")
      (node (ref "U7000") (pin "32") (pinfunction "SPICS0_32") (pintype "bidirectional"))
      (node (ref "U7001") (pin "1") (pinfunction "*CS_1") (pintype "input"))
    )
    (net (code "57") (name "Net-(U7000-SPID)") (class "Default")
      (node (ref "R7013") (pin "2") (pinfunction "2_2") (pintype "passive"))
      (node (ref "U7000") (pin "35") (pinfunction "SPID_35") (pintype "bidirectional"))
    )
    (net (code "58") (name "Net-(U7000-SPIHD)") (class "Default")
      (node (ref "R7009") (pin "2") (pinfunction "2_2") (pintype "passive"))
      (node (ref "U7000") (pin "30") (pinfunction "SPIHD_30") (pintype "bidirectional"))
    )
    (net (code "59") (name "Net-(U7000-SPIQ)") (class "Default")
      (node (ref "R7012") (pin "2") (pinfunction "2_2") (pintype "passive"))
      (node (ref "U7000") (pin "34") (pinfunction "SPIQ_34") (pintype "bidirectional"))
    )
    (net (code "60") (name "Net-(U7000-SPIWP)") (class "Default")
      (node (ref "R7010") (pin "2") (pinfunction "2_2") (pintype "passive"))
      (node (ref "U7000") (pin "31") (pinfunction "SPIWP_31") (pintype "bidirectional"))
    )
    (net (code "61") (name "Net-(U7000-U0RXD)") (class "Default")
      (node (ref "TP7004") (pin "1") (pinfunction "1_1") (pintype "passive"))
      (node (ref "U7000") (pin "50") (pinfunction "U0RXD_50") (pintype "bidirectional"))
    )
    (net (code "62") (name "Net-(U7000-U0TXD)") (class "Default")
      (node (ref "R7006") (pin "1") (pinfunction "1_1") (pintype "passive"))
      (node (ref "U7000") (pin "49") (pinfunction "U0TXD_49") (pintype "bidirectional"))
    )
    (net (code "63") (name "Net-(U7000-XTAL_N)") (class "Default")
      (node (ref "C7015") (pin "1") (pinfunction "1_1") (pintype "passive"))
      (node (ref "U7000") (pin "53") (pinfunction "XTAL_N_53") (pintype "output"))
      (node (ref "Y7000") (pin "3") (pinfunction "OSC2_3") (pintype "passive"))
    )
    (net (code "64") (name "Net-(U7000-XTAL_P)") (class "Default")
      (node (ref "C7001") (pin "1") (pinfunction "1_1") (pintype "passive"))
      (node (ref "U7000") (pin "54") (pinfunction "XTAL_P_54") (pintype "input"))
      (node (ref "Y7000") (pin "1") (pinfunction "OSC1_1") (pintype "passive"))
    )
    (net (code "65") (name "Net-(U7001-*HOLD(IO3))") (class "Default")
      (node (ref "R7009") (pin "1") (pinfunction "1_1") (pintype "passive"))
      (node (ref "U7001") (pin "7") (pinfunction "*HOLD(IO3)_7") (pintype "bidirectional"))
    )
    (net (code "66") (name "Net-(U7001-*WP(IO2))") (class "Default")
      (node (ref "R7010") (pin "1") (pinfunction "1_1") (pintype "passive"))
      (node (ref "U7001") (pin "3") (pinfunction "*WP(IO2)_3") (pintype "bidirectional"))
    )
    (net (code "67") (name "Net-(U7001-CLK)") (class "Default")
      (node (ref "R7011") (pin "1") (pinfunction "1_1") (pintype "passive"))
      (node (ref "U7001") (pin "6") (pinfunction "CLK_6") (pintype "input"))
    )
    (net (code "68") (name "Net-(U7001-DI(IO0))") (class "Default")
      (node (ref "R7013") (pin "1") (pinfunction "1_1") (pintype "passive"))
      (node (ref "U7001") (pin "5") (pinfunction "DI(IO0)_5") (pintype "bidirectional"))
    )
    (net (code "69") (name "Net-(U7001-DO(IO1))") (class "Default")
      (node (ref "R7012") (pin "1") (pinfunction "1_1") (pintype "passive"))
      (node (ref "U7001") (pin "2") (pinfunction "DO(IO1)_2") (pintype "bidirectional"))
    )
    (net (code "70") (name "Net-(U7004-CS#)") (class "Default")
      (node (ref "U7004") (pin "1") (pinfunction "CS#_1") (pintype "passive"))
      (node (ref "U7005") (pin "1") (pinfunction "A1_1") (pintype "bidirectional"))
    )
    (net (code "71") (name "Net-(U7004-RESET#{slash}SIO3)") (class "Default")
      (node (ref "R7024") (pin "1") (pinfunction "1_1") (pintype "passive"))
      (node (ref "U7004") (pin "7") (pinfunction "RESET#/SIO3_7") (pintype "passive"))
      (node (ref "U7005") (pin "6") (pinfunction "A5_6") (pintype "bidirectional"))
    )
    (net (code "72") (name "Net-(U7004-SCLK)") (class "Default")
      (node (ref "U7004") (pin "6") (pinfunction "SCLK_6") (pintype "passive"))
      (node (ref "U7005") (pin "7") (pinfunction "A6_7") (pintype "bidirectional"))
    )
    (net (code "73") (name "Net-(U7004-SI{slash}SIO0)") (class "Default")
      (node (ref "U7004") (pin "5") (pinfunction "SI/SIO0_5") (pintype "passive"))
      (node (ref "U7005") (pin "3") (pinfunction "A2_3") (pintype "bidirectional"))
    )
    (net (code "74") (name "Net-(U7004-SO{slash}SIO1)") (class "Default")
      (node (ref "U7004") (pin "2") (pinfunction "SO/SIO1_2") (pintype "passive"))
      (node (ref "U7005") (pin "4") (pinfunction "A3_4") (pintype "bidirectional"))
    )
    (net (code "75") (name "Net-(U7004-WP#{slash}SIO2)") (class "Default")
      (node (ref "U7004") (pin "3") (pinfunction "WP#/SIO2_3") (pintype "passive"))
      (node (ref "U7005") (pin "5") (pinfunction "A4_5") (pintype "bidirectional"))
    )
    (net (code "76") (name "VDD_HV_A") (class "Default")
      (node (ref "C7027") (pin "1") (pinfunction "1_1") (pintype "passive"))
      (node (ref "C7029") (pin "1") (pinfunction "1_1") (pintype "passive"))
      (node (ref "U7005") (pin "15") (pinfunction "VCCB_15") (pintype "power_in"))
      (node (ref "U7006") (pin "15") (pinfunction "VCCB_15") (pintype "power_in"))
    )
    (net (code "77") (name "VDD_HV_B") (class "Default")
      (node (ref "C7017") (pin "1") (pinfunction "1_1") (pintype "passive"))
      (node (ref "U7002") (pin "5") (pinfunction "VDDIO_5") (pintype "power_in"))
    )
    (net (code "78") (name "VDD_SPI") (class "Default")
      (node (ref "C7013") (pin "1") (pinfunction "1_1") (pintype "passive"))
      (node (ref "C7014") (pin "1") (pinfunction "1_1") (pintype "passive"))
      (node (ref "C7016") (pin "1") (pinfunction "1_1") (pintype "passive"))
      (node (ref "U7000") (pin "29") (pinfunction "VDD_SPI_29") (pintype "power_in"))
      (node (ref "U7001") (pin "8") (pinfunction "VCC_8") (pintype "power_in"))
    )
    (net (code "79") (name "VREG_3P3") (class "Default")
      (node (ref "C7004") (pin "1") (pinfunction "1_1") (pintype "passive"))
      (node (ref "C7005") (pin "1") (pinfunction "1_1") (pintype "passive"))
      (node (ref "C7006") (pin "1") (pinfunction "1_1") (pintype "passive"))
      (node (ref "C7007") (pin "1") (pinfunction "1_1") (pintype "passive"))
      (node (ref "C7008") (pin "1") (pinfunction "1_1") (pintype "passive"))
      (node (ref "C7009") (pin "1") (pinfunction "1_1") (pintype "passive"))
      (node (ref "C7010") (pin "1") (pinfunction "1_1") (pintype "passive"))
      (node (ref "C7018") (pin "1") (pinfunction "1_1") (pintype "passive"))
      (node (ref "C7019") (pin "1") (pinfunction "1_1") (pintype "passive"))
      (node (ref "C7025") (pin "1") (pinfunction "1_1") (pintype "passive"))
      (node (ref "C7026") (pin "1") (pinfunction "1_1") (pintype "passive"))
      (node (ref "C7028") (pin "1") (pinfunction "1_1") (pintype "passive"))
      (node (ref "C7030") (pin "1") (pinfunction "1_1") (pintype "passive"))
      (node (ref "FB7000") (pin "2") (pinfunction "2_2") (pintype "passive"))
      (node (ref "R7000") (pin "2") (pinfunction "2_2") (pintype "passive"))
      (node (ref "R7003") (pin "2") (pinfunction "2_2") (pintype "passive"))
      (node (ref "R7004") (pin "2") (pinfunction "2_2") (pintype "passive"))
      (node (ref "R7016") (pin "2") (pinfunction "2_2") (pintype "passive"))
      (node (ref "R7017") (pin "2") (pinfunction "2_2") (pintype "passive"))
      (node (ref "R7024") (pin "2") (pinfunction "2_2") (pintype "passive"))
      (node (ref "U7000") (pin "20") (pinfunction "VDD3P3_RTC_20") (pintype "power_in"))
      (node (ref "U7000") (pin "46") (pinfunction "VDD3P3_CPU_46") (pintype "power_in"))
      (node (ref "U7000") (pin "55") (pinfunction "VDDA1_55") (pintype "power_in"))
      (node (ref "U7000") (pin "56") (pinfunction "VDDA2_56") (pintype "power_in"))
      (node (ref "U7002") (pin "8") (pinfunction "VDD_8") (pintype "power_in"))
      (node (ref "U7004") (pin "8") (pinfunction "VCC_8") (pintype "passive"))
      (node (ref "U7005") (pin "2") (pinfunction "VCCA_2") (pintype "power_in"))
      (node (ref "U7005") (pin "8") (pinfunction "OE_8") (pintype "output"))
      (node (ref "U7006") (pin "2") (pinfunction "VCCA_2") (pintype "power_in"))
      (node (ref "U7006") (pin "8") (pinfunction "OE_8") (pintype "output"))
    )
    (net (code "80") (name "VREG_5P0") (class "Default")
      (node (ref "C7020") (pin "1") (pinfunction "1_1") (pintype "passive"))
      (node (ref "C7021") (pin "1") (pinfunction "1_1") (pintype "passive"))
      (node (ref "CN7002") (pin "3") (pinfunction "VIN_3") (pintype "power_in"))
    )
    (net (code "81") (name "VUSB_5P0") (class "Default")
      (node (ref "C7031") (pin "1") (pinfunction "1_1") (pintype "passive"))
      (node (ref "CN7001") (pin "A4_B9") (pinfunction "VBUS_A4_B9") (pintype "power_in"))
      (node (ref "CN7001") (pin "B4_A9") (pinfunction "VBUS_B4_A9") (pintype "power_in"))
    )
    (net (code "82") (name "unconnected-(CN7001-SBU1-PadA8)") (class "Default")
      (node (ref "CN7001") (pin "A8") (pinfunction "SBU1_A8") (pintype "bidirectional"))
    )
    (net (code "83") (name "unconnected-(CN7001-SBU2-PadB8)") (class "Default")
      (node (ref "CN7001") (pin "B8") (pinfunction "SBU2_B8") (pintype "bidirectional"))
    )
    (net (code "84") (name "unconnected-(CN7002-GPIO1-Pad7)") (class "Default")
      (node (ref "CN7002") (pin "7") (pinfunction "GPIO1_7") (pintype "bidirectional"))
    )
    (net (code "85") (name "unconnected-(CN7002-GPIO2-Pad9)") (class "Default")
      (node (ref "CN7002") (pin "9") (pinfunction "GPIO2_9") (pintype "power_in"))
    )
    (net (code "86") (name "unconnected-(CN7002-GPIO3-Pad6)") (class "Default")
      (node (ref "CN7002") (pin "6") (pinfunction "GPIO3_6") (pintype "bidirectional"))
    )
    (net (code "87") (name "unconnected-(CN7002-GPIO4-Pad10)") (class "Default")
      (node (ref "CN7002") (pin "10") (pinfunction "GPIO4_10") (pintype "power_in"))
    )
    (net (code "88") (name "unconnected-(CN7002-USBDM-Pad1)") (class "Default")
      (node (ref "CN7002") (pin "1") (pinfunction "USBDM_1") (pintype "passive"))
    )
    (net (code "89") (name "unconnected-(CN7002-USBDP-Pad2)") (class "Default")
      (node (ref "CN7002") (pin "2") (pinfunction "USBDP_2") (pintype "passive"))
    )
    (net (code "90") (name "unconnected-(U7000-GPIO9-Pad14)") (class "Default")
      (node (ref "U7000") (pin "14") (pinfunction "GPIO9_14") (pintype "bidirectional"))
    )
    (net (code "91") (name "unconnected-(U7000-GPIO10-Pad15)") (class "Default")
      (node (ref "U7000") (pin "15") (pinfunction "GPIO10_15") (pintype "bidirectional"))
    )
    (net (code "92") (name "unconnected-(U7000-GPIO11-Pad16)") (class "Default")
      (node (ref "U7000") (pin "16") (pinfunction "GPIO11_16") (pintype "bidirectional"))
    )
    (net (code "93") (name "unconnected-(U7000-SPICS1-Pad28)") (class "Default")
      (node (ref "U7000") (pin "28") (pinfunction "SPICS1_28") (pintype "bidirectional"))
    )
    (net (code "94") (name "unconnected-(U7000-XTAL_32K_N-Pad22)") (class "Default")
      (node (ref "U7000") (pin "22") (pinfunction "XTAL_32K_N_22") (pintype "bidirectional"))
    )
    (net (code "95") (name "unconnected-(U7000-XTAL_32K_P-Pad21)") (class "Default")
      (node (ref "U7000") (pin "21") (pinfunction "XTAL_32K_P_21") (pintype "bidirectional"))
    )
    (net (code "96") (name "unconnected-(U7002-ASCX-Pad3)") (class "Default")
      (node (ref "U7002") (pin "3") (pinfunction "ASCX_3") (pintype "bidirectional"))
    )
    (net (code "97") (name "unconnected-(U7002-ASDX-Pad2)") (class "Default")
      (node (ref "U7002") (pin "2") (pinfunction "ASDX_2") (pintype "bidirectional"))
    )
    (net (code "98") (name "unconnected-(U7002-CSB-Pad12)") (class "Default")
      (node (ref "U7002") (pin "12") (pinfunction "CSB_12") (pintype "input"))
    )
    (net (code "99") (name "unconnected-(U7002-INT1-Pad4)") (class "Default")
      (node (ref "U7002") (pin "4") (pinfunction "INT1_4") (pintype "bidirectional"))
    )
    (net (code "100") (name "unconnected-(U7002-INT2-Pad9)") (class "Default")
      (node (ref "U7002") (pin "9") (pinfunction "INT2_9") (pintype "bidirectional"))
    )
    (net (code "101") (name "unconnected-(U7002-OSCB-Pad10)") (class "Default")
      (node (ref "U7002") (pin "10") (pinfunction "OSCB_10") (pintype "input"))
    )
    (net (code "102") (name "unconnected-(U7002-OSDO-Pad11)") (class "Default")
      (node (ref "U7002") (pin "11") (pinfunction "OSDO_11") (pintype "output"))
    )
    (net (code "103") (name "unconnected-(U7002-SDO-Pad1)") (class "Default")
      (node (ref "U7002") (pin "1") (pinfunction "SDO_1") (pintype "bidirectional"))
    )
    (net (code "104") (name "unconnected-(U7006-A6-Pad7)") (class "Default")
      (node (ref "U7006") (pin "7") (pinfunction "A6_7") (pintype "bidirectional"))
    )
    (net (code "105") (name "unconnected-(U7006-B6-Pad10)") (class "Default")
      (node (ref "U7006") (pin "10") (pinfunction "B6_10") (pintype "bidirectional"))
    )
  )
)
